# adapter_trs_rev_a.net
KiCad netlist of a schematic drawn in EAGLE
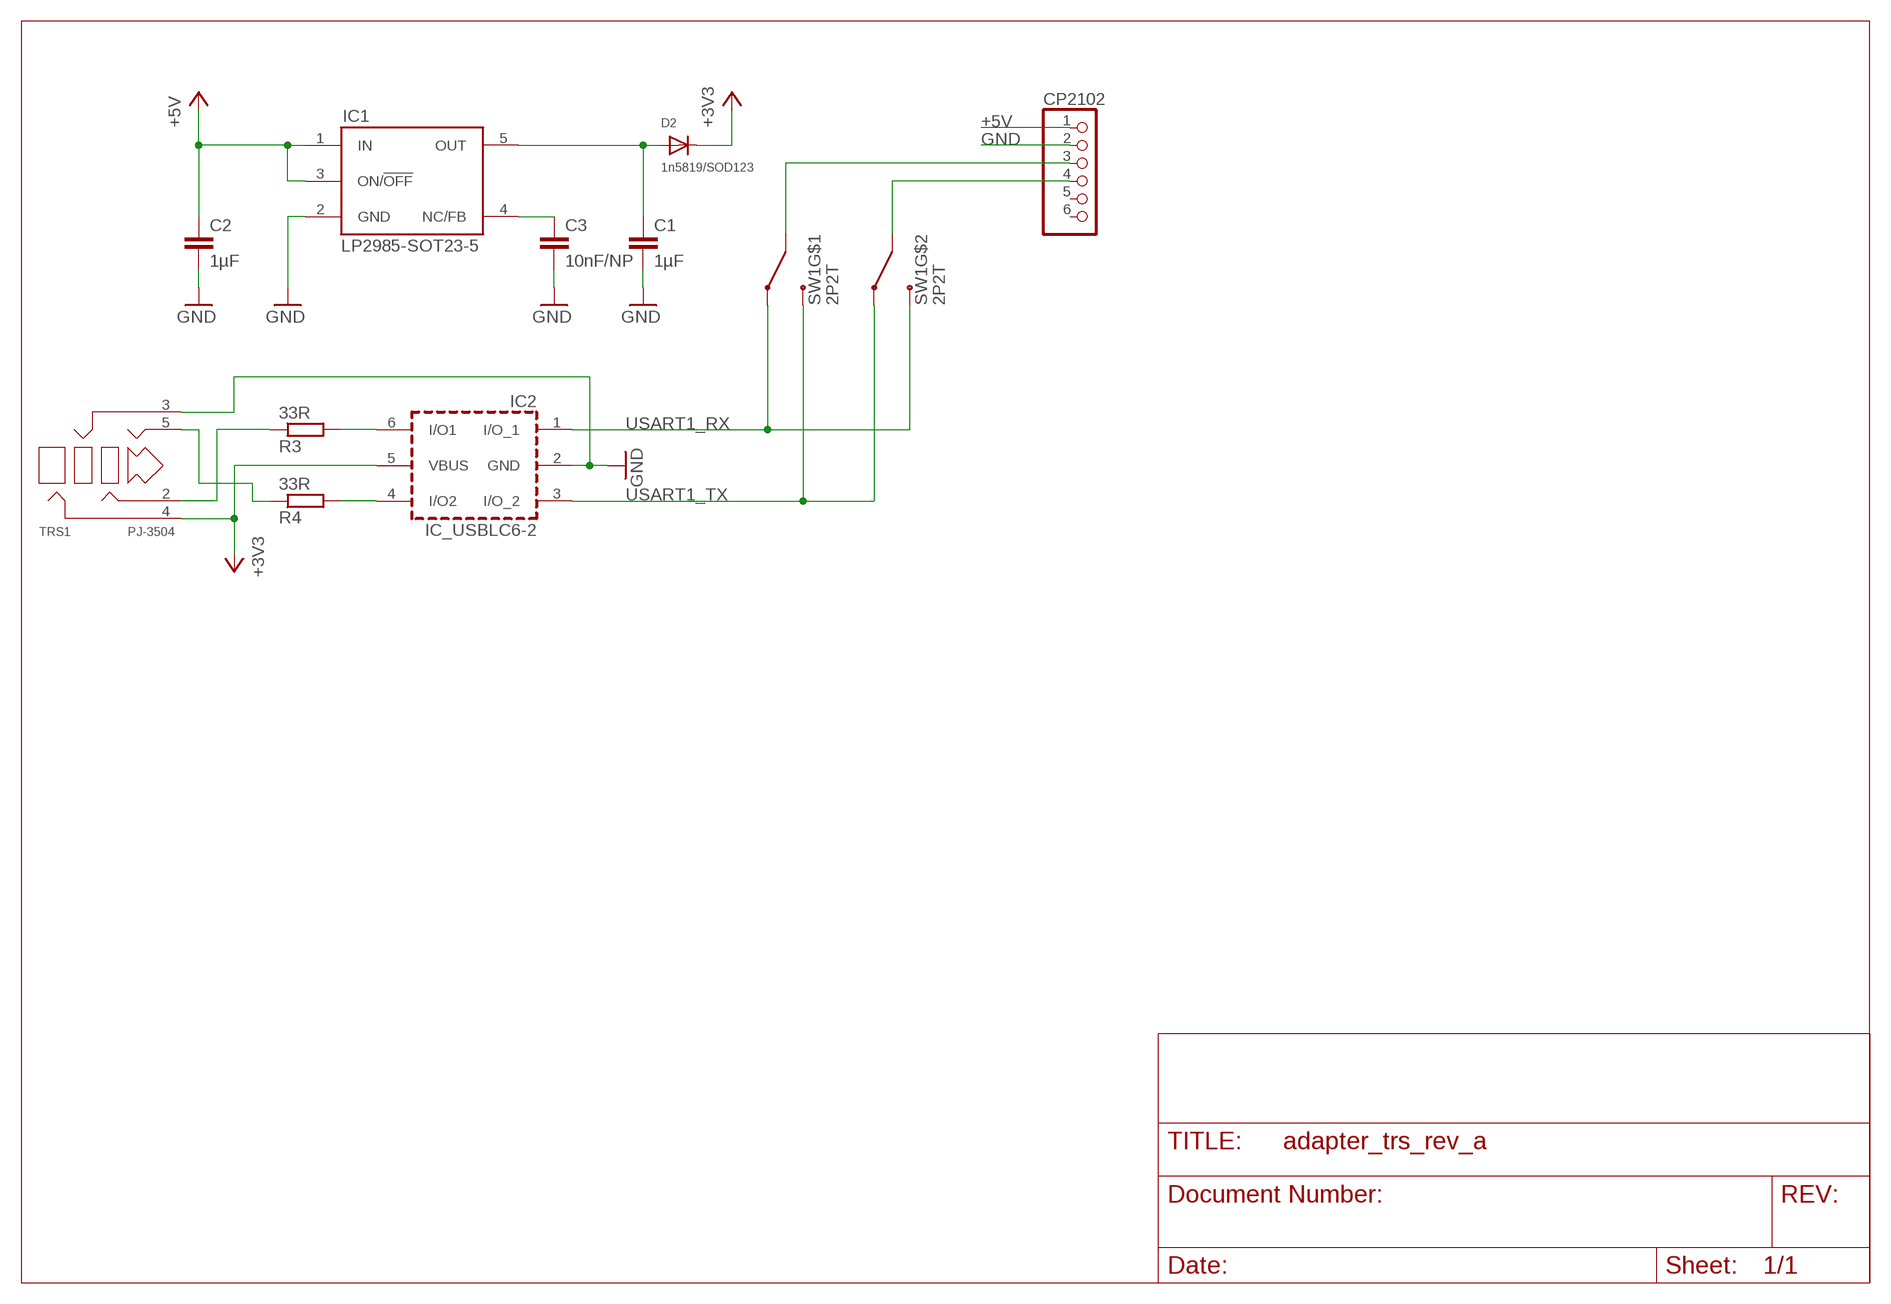
[diagram p0: schematic, sheet 1]

(export (version "E")
  (design (tool "Eeschema 10.0.6"))
  (components
    (comp (ref "C1")
      (value "1µF")
      (footprint "eagle-import:C0603")
      (libsource (lib "eagle-import") (part "C-EUC0603"))
    )
    (comp (ref "C2")
      (value "1µF")
      (footprint "eagle-import:C0603")
      (libsource (lib "eagle-import") (part "C-EUC0603"))
    )
    (comp (ref "C3")
      (value "10nF/NP")
      (footprint "eagle-import:C0603")
      (libsource (lib "eagle-import") (part "C-EUC0603"))
    )
    (comp (ref "CP2102")
      (value "HEADER-1X6ROUND")
      (footprint "eagle-import:1X06_ROUND")
      (libsource (lib "eagle-import") (part "HEADER-1X6ROUND"))
    )
    (comp (ref "D2")
      (value "1n5819/SOD123")
      (footprint "eagle-import:SOD-123")
      (libsource (lib "eagle-import") (part "DIODESOD-123"))
    )
    (comp (ref "IC1")
      (value "LP2985-SOT23-5")
      (footprint "eagle-import:SOT23-5")
      (libsource (lib "eagle-import") (part "LP2985-SOT23-5"))
    )
    (comp (ref "IC2")
      (value "IC_USBLC6-2")
      (footprint "eagle-import:SOT-23-6L")
      (libsource (lib "eagle-import") (part "IC_USBLC6-2"))
    )
    (comp (ref "R3")
      (value "33R")
      (footprint "eagle-import:R0603")
      (libsource (lib "eagle-import") (part "R-EU_R0603"))
    )
    (comp (ref "R4")
      (value "33R")
      (footprint "eagle-import:R0603")
      (libsource (lib "eagle-import") (part "R-EU_R0603"))
    )
    (comp (ref "SW1")
      (value "2P2T")
      (footprint "eagle-import:MSS22D18")
      (libsource (lib "eagle-import") (part "2P2T"))
    )
    (comp (ref "TRS1")
      (value "PJ-3504")
      (footprint "eagle-import:YD-PJ-3504")
      (libsource (lib "eagle-import") (part "PJ-3504"))
    )
  )
  (nets
    (net (code "1") (name "+3V3") (class "Default")
      (node (ref "D2") (pin "C") (pinfunction "C_C") (pintype "passive"))
      (node (ref "IC2") (pin "5") (pinfunction "VBUS_5") (pintype "bidirectional"))
      (node (ref "TRS1") (pin "4") (pinfunction "4_4") (pintype "bidirectional"))
    )
    (net (code "2") (name "+5V") (class "Default")
      (node (ref "C2") (pin "1") (pinfunction "1_1") (pintype "passive"))
      (node (ref "CP2102") (pin "1") (pinfunction "1_1") (pintype "passive"))
      (node (ref "IC1") (pin "1") (pinfunction "IN_1") (pintype "bidirectional"))
      (node (ref "IC1") (pin "3") (pinfunction "ON/~{OFF}_3") (pintype "bidirectional"))
    )
    (net (code "3") (name "/USART1_RX") (class "Default")
      (node (ref "IC2") (pin "1") (pinfunction "I/O_1_1") (pintype "bidirectional"))
      (node (ref "SW1") (pin "A1") (pinfunction "A_A1") (pintype "bidirectional"))
      (node (ref "SW1") (pin "B2") (pinfunction "B_B2") (pintype "bidirectional"))
    )
    (net (code "4") (name "/USART1_TX") (class "Default")
      (node (ref "IC2") (pin "3") (pinfunction "I/O_2_3") (pintype "bidirectional"))
      (node (ref "SW1") (pin "A2") (pinfunction "A_A2") (pintype "bidirectional"))
      (node (ref "SW1") (pin "B1") (pinfunction "B_B1") (pintype "bidirectional"))
    )
    (net (code "5") (name "GND") (class "Default")
      (node (ref "C1") (pin "2") (pinfunction "2_2") (pintype "passive"))
      (node (ref "C2") (pin "2") (pinfunction "2_2") (pintype "passive"))
      (node (ref "C3") (pin "2") (pinfunction "2_2") (pintype "passive"))
      (node (ref "CP2102") (pin "2") (pinfunction "2_2") (pintype "passive"))
      (node (ref "IC1") (pin "2") (pinfunction "GND_2") (pintype "bidirectional"))
      (node (ref "IC2") (pin "2") (pinfunction "GND_2") (pintype "bidirectional"))
      (node (ref "TRS1") (pin "3") (pinfunction "3_3") (pintype "bidirectional"))
    )
    (net (code "6") (name "Net-(IC1-NC{slash}FB)") (class "Default")
      (node (ref "C3") (pin "1") (pinfunction "1_1") (pintype "passive"))
      (node (ref "IC1") (pin "4") (pinfunction "NC/FB_4") (pintype "bidirectional"))
    )
    (net (code "7") (name "Net-(IC1-OUT)") (class "Default")
      (node (ref "C1") (pin "1") (pinfunction "1_1") (pintype "passive"))
      (node (ref "D2") (pin "A") (pinfunction "A_A") (pintype "passive"))
      (node (ref "IC1") (pin "5") (pinfunction "OUT_5") (pintype "bidirectional"))
    )
    (net (code "8") (name "Net-(IC2-I{slash}O1)") (class "Default")
      (node (ref "IC2") (pin "6") (pinfunction "I/O1_6") (pintype "bidirectional"))
      (node (ref "R3") (pin "2") (pinfunction "2_2") (pintype "passive"))
    )
    (net (code "9") (name "Net-(IC2-I{slash}O2)") (class "Default")
      (node (ref "IC2") (pin "4") (pinfunction "I/O2_4") (pintype "bidirectional"))
      (node (ref "R4") (pin "2") (pinfunction "2_2") (pintype "passive"))
    )
    (net (code "10") (name "Net-(R3-Pad1)") (class "Default")
      (node (ref "R3") (pin "1") (pinfunction "1_1") (pintype "passive"))
      (node (ref "TRS1") (pin "2") (pinfunction "2_2") (pintype "bidirectional"))
    )
    (net (code "11") (name "Net-(R4-Pad1)") (class "Default")
      (node (ref "R4") (pin "1") (pinfunction "1_1") (pintype "passive"))
      (node (ref "TRS1") (pin "5") (pinfunction "5_5") (pintype "bidirectional"))
    )
    (net (code "12") (name "Net-(SW1A-C)") (class "Default")
      (node (ref "CP2102") (pin "3") (pinfunction "3_3") (pintype "passive"))
      (node (ref "SW1") (pin "C1") (pinfunction "C_C1") (pintype "bidirectional"))
    )
    (net (code "13") (name "Net-(SW1B-C)") (class "Default")
      (node (ref "CP2102") (pin "4") (pinfunction "4_4") (pintype "passive"))
      (node (ref "SW1") (pin "C2") (pinfunction "C_C2") (pintype "bidirectional"))
    )
    (net (code "14") (name "unconnected-(CP2102-Pad5)") (class "Default")
      (node (ref "CP2102") (pin "5") (pinfunction "5_5") (pintype "passive"))
    )
    (net (code "15") (name "unconnected-(CP2102-Pad6)") (class "Default")
      (node (ref "CP2102") (pin "6") (pinfunction "6_6") (pintype "passive"))
    )
  )
)
